# Schematic.net
KiCad netlist of a schematic drawn in Altium Designer
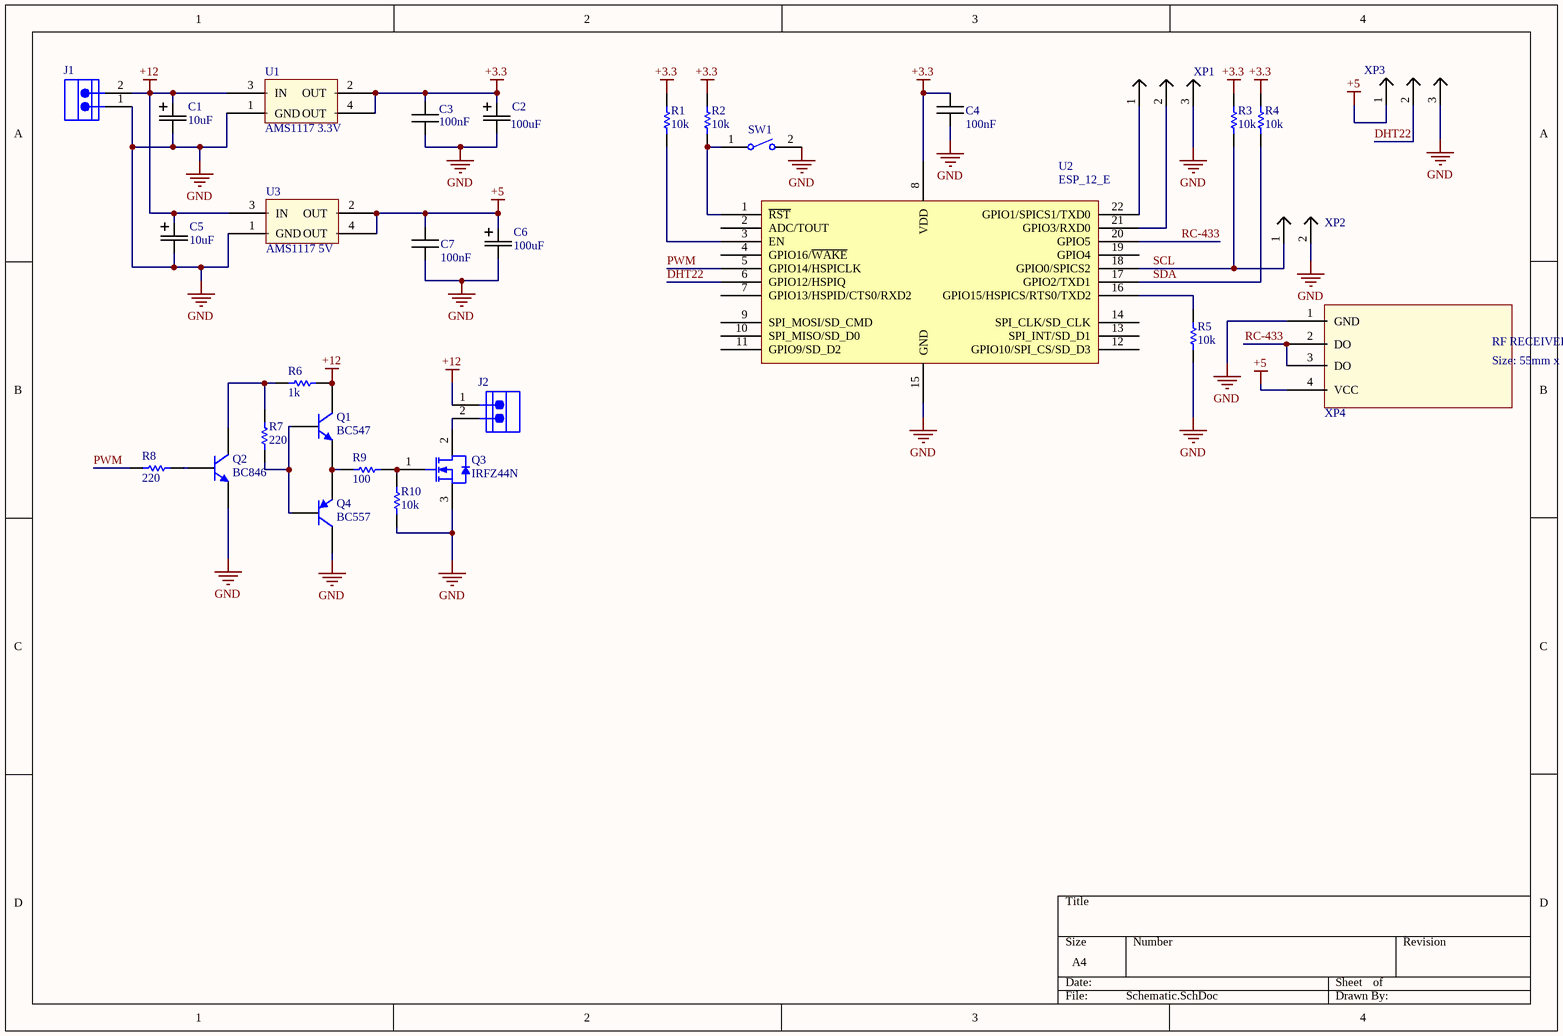
[diagram p0: Schematic.SchDoc]

(export (version "E")
  (design (tool "Eeschema 10.0.6"))
  (components
    (comp (ref "C1")
      (value "CAP_ELEC_5*11")
      (footprint "CAP_ELEC_5*11")
      (description "Electrolitic capacitor")
      (fields (field (name "VAL") "10uF"))
      (libsource (lib "altium-import") (part "root_1_CAP_ELEC_5*11_"))
    )
    (comp (ref "C2")
      (value "CAP_ELEC_8*11")
      (footprint "CAP_ELEC_8*11")
      (description "Electrolitic capacitor")
      (fields (field (name "VAL") "100uF"))
      (libsource (lib "altium-import") (part "root_1_CAP_ELEC_8*11_"))
    )
    (comp (ref "C3")
      (value "CAP_SMD")
      (footprint "CAP0805")
      (description "Ceramic capacitor, 0805")
      (fields (field (name "VAL") "100nF"))
      (libsource (lib "altium-import") (part "root_1_CAP_SMD_"))
    )
    (comp (ref "C4")
      (value "CAP_SMD")
      (footprint "CAP0805")
      (description "Ceramic capacitor, 0805")
      (fields (field (name "VAL") "100nF"))
      (libsource (lib "altium-import") (part "root_1_CAP_SMD_"))
    )
    (comp (ref "C5")
      (value "CAP_ELEC_5*11")
      (footprint "CAP_ELEC_5*11")
      (description "Electrolitic capacitor")
      (fields (field (name "VAL") "10uF"))
      (libsource (lib "altium-import") (part "root_1_CAP_ELEC_5*11_"))
    )
    (comp (ref "C6")
      (value "CAP_ELEC_8*11")
      (footprint "CAP_ELEC_8*11")
      (description "Electrolitic capacitor")
      (fields (field (name "VAL") "100uF"))
      (libsource (lib "altium-import") (part "root_1_CAP_ELEC_8*11_"))
    )
    (comp (ref "C7")
      (value "CAP_SMD")
      (footprint "CAP0805")
      (description "Ceramic capacitor, 0805")
      (fields (field (name "VAL") "100nF"))
      (libsource (lib "altium-import") (part "root_1_CAP_SMD_"))
    )
    (comp (ref "J1")
      (value "~")
      (footprint "KF350-3.5-02P")
      (fields
        (field (name "MANUFACTURER") "Cixi KaiFeng")
        (field (name "PARTNUMBER") "KF120-02P-14")
        (field (name "CONTACT") "Brass")
      )
      (libsource (lib "altium-import") (part "root_1_Terminal_2_"))
    )
    (comp (ref "J2")
      (value "~")
      (footprint "KF350-3.5-02P")
      (fields
        (field (name "MANUFACTURER") "Cixi KaiFeng")
        (field (name "PARTNUMBER") "KF120-02P-14")
        (field (name "CONTACT") "Brass")
      )
      (libsource (lib "altium-import") (part "root_3_Terminal_2_"))
    )
    (comp (ref "Q1")
      (value "BC547")
      (footprint "TO-92A")
      (description "NPN Bipolar Transistor")
      (fields (field (name "PUBLISHER") "Altium Limited"))
      (libsource (lib "altium-import") (part "root_0_BC547_"))
    )
    (comp (ref "Q2")
      (value "BC846")
      (footprint "SOT23 - 123")
      (description "NPN Bipolar Transistor")
      (fields (field (name "PUBLISHER") "Altium Limited"))
      (libsource (lib "altium-import") (part "root_0_BC846_"))
    )
    (comp (ref "Q3")
      (value "IRFZ44N")
      (footprint "TO-220")
      (description "N-channel Enhancement Mode Power MOSFET 49A/55V")
      (libsource (lib "altium-import") (part "root_0_IRFZ44N_"))
    )
    (comp (ref "Q4")
      (value "BC557")
      (footprint "TO-92A")
      (description "PNP Transistor")
      (fields (field (name "PUBLISHER") "Altium Limited"))
      (libsource (lib "altium-import") (part "root_2_mirrored_BC557_"))
    )
    (comp (ref "R1")
      (value "RES_SMD")
      (footprint "RES0805")
      (fields (field (name "VAL") "10k"))
      (libsource (lib "altium-import") (part "root_1_RES_SMD_"))
    )
    (comp (ref "R2")
      (value "RES_SMD")
      (footprint "RES0805")
      (fields (field (name "VAL") "10k"))
      (libsource (lib "altium-import") (part "root_1_RES_SMD_"))
    )
    (comp (ref "R3")
      (value "RES_SMD")
      (footprint "RES0805")
      (fields (field (name "VAL") "10k"))
      (libsource (lib "altium-import") (part "root_1_RES_SMD_"))
    )
    (comp (ref "R4")
      (value "RES_SMD")
      (footprint "RES0805")
      (fields (field (name "VAL") "10k"))
      (libsource (lib "altium-import") (part "root_1_RES_SMD_"))
    )
    (comp (ref "R5")
      (value "RES_SMD")
      (footprint "RES0805")
      (fields (field (name "VAL") "10k"))
      (libsource (lib "altium-import") (part "root_1_RES_SMD_"))
    )
    (comp (ref "R6")
      (value "RES_SMD")
      (footprint "RES0805")
      (fields (field (name "VAL") "1k"))
      (libsource (lib "altium-import") (part "root_2_RES_SMD_"))
    )
    (comp (ref "R7")
      (value "RES_SMD")
      (footprint "RES0805")
      (fields (field (name "VAL") "220"))
      (libsource (lib "altium-import") (part "root_3_RES_SMD_"))
    )
    (comp (ref "R8")
      (value "RES_SMD")
      (footprint "RES0805")
      (fields (field (name "VAL") "220"))
      (libsource (lib "altium-import") (part "root_2_RES_SMD_"))
    )
    (comp (ref "R9")
      (value "RES_SMD")
      (footprint "RES0805")
      (fields (field (name "VAL") "100"))
      (libsource (lib "altium-import") (part "root_2_RES_SMD_"))
    )
    (comp (ref "R10")
      (value "RES_SMD")
      (footprint "RES0805")
      (fields (field (name "VAL") "10k"))
      (libsource (lib "altium-import") (part "root_3_RES_SMD_"))
    )
    (comp (ref "SW1")
      (value "~")
      (footprint "SMD_BUT_6.3mm")
      (description "SMD Switch")
      (fields (field (name "MANUFACTURER") "TE Connectivity"))
      (libsource (lib "altium-import") (part "root_0_Button_2_SMD_"))
    )
    (comp (ref "U1")
      (value "AMS1117 3.3V")
      (footprint "SOT223-4")
      (description "Voltage regulator")
      (libsource (lib "altium-import") (part "root_0_AMS1117_"))
    )
    (comp (ref "U2")
      (value "ESP_12_E")
      (footprint "ESP_12_E")
      (description "ESP-12 Wi-Fi Module by AI-Thinker")
      (libsource (lib "altium-import") (part "root_0_ESP_12_E_"))
    )
    (comp (ref "U3")
      (value "AMS1117 5V")
      (footprint "SOT223-4")
      (description "Voltage regulator")
      (libsource (lib "altium-import") (part "root_0_AMS1117_"))
    )
    (comp (ref "XP1")
      (value "PLS-03")
      (footprint "PLS-03")
      (libsource (lib "altium-import") (part "root_1_PLS-03_"))
    )
    (comp (ref "XP2")
      (value "PLS-02")
      (footprint "PLS-02")
      (libsource (lib "altium-import") (part "root_1_PLS-02_"))
    )
    (comp (ref "XP3")
      (value "PBS-03")
      (footprint "PBS-03")
      (libsource (lib "altium-import") (part "root_1_PBS-03_"))
    )
    (comp (ref "XP4")
      (value "RF_RECEIVER")
      (footprint "RF RECEIVER")
      (libsource (lib "altium-import") (part "root_0_mirrored_RF_RECEIVER_"))
    )
  )
  (nets
    (net (code "1") (name "+3.3") (class "Default")
      (node (ref "C2") (pin "2") (pinfunction "2_2") (pintype "passive"))
      (node (ref "C3") (pin "2") (pinfunction "2_2") (pintype "passive"))
      (node (ref "C4") (pin "2") (pinfunction "2_2") (pintype "passive"))
      (node (ref "R1") (pin "2") (pinfunction "2_2") (pintype "passive"))
      (node (ref "R2") (pin "2") (pinfunction "2_2") (pintype "passive"))
      (node (ref "R3") (pin "2") (pinfunction "2_2") (pintype "passive"))
      (node (ref "R4") (pin "2") (pinfunction "2_2") (pintype "passive"))
      (node (ref "U1") (pin "2") (pinfunction "OUT_2") (pintype "passive"))
      (node (ref "U1") (pin "4") (pinfunction "OUT_4") (pintype "passive"))
      (node (ref "U2") (pin "8") (pinfunction "VDD_8") (pintype "passive"))
    )
    (net (code "2") (name "+5") (class "Default")
      (node (ref "C6") (pin "2") (pinfunction "2_2") (pintype "passive"))
      (node (ref "C7") (pin "2") (pinfunction "2_2") (pintype "passive"))
      (node (ref "U3") (pin "2") (pinfunction "OUT_2") (pintype "passive"))
      (node (ref "U3") (pin "4") (pinfunction "OUT_4") (pintype "passive"))
      (node (ref "XP3") (pin "1") (pinfunction "1_1") (pintype "passive"))
      (node (ref "XP4") (pin "4") (pinfunction "VCC_4") (pintype "passive"))
    )
    (net (code "3") (name "+12") (class "Default")
      (node (ref "C1") (pin "2") (pinfunction "2_2") (pintype "passive"))
      (node (ref "C5") (pin "2") (pinfunction "2_2") (pintype "passive"))
      (node (ref "J1") (pin "2") (pinfunction "2_2") (pintype "passive"))
      (node (ref "J2") (pin "1") (pinfunction "1_1") (pintype "passive"))
      (node (ref "Q1") (pin "1") (pinfunction "C_1") (pintype "passive"))
      (node (ref "R6") (pin "1") (pinfunction "1_1") (pintype "passive"))
      (node (ref "U1") (pin "3") (pinfunction "IN_3") (pintype "passive"))
      (node (ref "U3") (pin "3") (pinfunction "IN_3") (pintype "passive"))
    )
    (net (code "4") (name "/DHT22") (class "Default")
      (node (ref "U2") (pin "6") (pinfunction "GPIO12/HSPIQ_6") (pintype "passive"))
      (node (ref "XP3") (pin "2") (pinfunction "2_2") (pintype "passive"))
    )
    (net (code "5") (name "/PWM") (class "Default")
      (node (ref "R8") (pin "2") (pinfunction "2_2") (pintype "passive"))
      (node (ref "U2") (pin "5") (pinfunction "GPIO14/HSPICLK_5") (pintype "passive"))
    )
    (net (code "6") (name "/RC-433") (class "Default")
      (node (ref "U2") (pin "20") (pinfunction "GPIO5_20") (pintype "passive"))
      (node (ref "XP4") (pin "2") (pinfunction "DO_2") (pintype "passive"))
      (node (ref "XP4") (pin "3") (pinfunction "DO_3") (pintype "passive"))
    )
    (net (code "7") (name "/SCL") (class "Default")
      (node (ref "R3") (pin "1") (pinfunction "1_1") (pintype "passive"))
      (node (ref "U2") (pin "18") (pinfunction "GPIO0/SPICS2_18") (pintype "passive"))
      (node (ref "XP2") (pin "1") (pinfunction "1_1") (pintype "passive"))
    )
    (net (code "8") (name "/SDA") (class "Default")
      (node (ref "R4") (pin "1") (pinfunction "1_1") (pintype "passive"))
      (node (ref "U2") (pin "17") (pinfunction "GPIO2/TXD1_17") (pintype "passive"))
    )
    (net (code "9") (name "GND") (class "Default")
      (node (ref "C1") (pin "1") (pinfunction "1_1") (pintype "passive"))
      (node (ref "C2") (pin "1") (pinfunction "1_1") (pintype "passive"))
      (node (ref "C3") (pin "1") (pinfunction "1_1") (pintype "passive"))
      (node (ref "C4") (pin "1") (pinfunction "1_1") (pintype "passive"))
      (node (ref "C5") (pin "1") (pinfunction "1_1") (pintype "passive"))
      (node (ref "C6") (pin "1") (pinfunction "1_1") (pintype "passive"))
      (node (ref "C7") (pin "1") (pinfunction "1_1") (pintype "passive"))
      (node (ref "J1") (pin "1") (pinfunction "1_1") (pintype "passive"))
      (node (ref "Q2") (pin "3") (pinfunction "E_3") (pintype "passive"))
      (node (ref "Q3") (pin "3") (pinfunction "S_3") (pintype "passive"))
      (node (ref "Q4") (pin "1") (pinfunction "C_1") (pintype "passive"))
      (node (ref "R10") (pin "2") (pinfunction "2_2") (pintype "passive"))
      (node (ref "R5") (pin "1") (pinfunction "1_1") (pintype "passive"))
      (node (ref "SW1") (pin "2") (pinfunction "2_2") (pintype "passive"))
      (node (ref "U1") (pin "1") (pinfunction "GND_1") (pintype "passive"))
      (node (ref "U2") (pin "15") (pinfunction "GND_15") (pintype "passive"))
      (node (ref "U3") (pin "1") (pinfunction "GND_1") (pintype "passive"))
      (node (ref "XP1") (pin "3") (pinfunction "3_3") (pintype "passive"))
      (node (ref "XP2") (pin "2") (pinfunction "2_2") (pintype "passive"))
      (node (ref "XP3") (pin "3") (pinfunction "3_3") (pintype "passive"))
      (node (ref "XP4") (pin "1") (pinfunction "GND_1") (pintype "passive"))
    )
    (net (code "10") (name "Net-(Q1-B)") (class "Default")
      (node (ref "Q1") (pin "2") (pinfunction "B_2") (pintype "passive"))
      (node (ref "Q4") (pin "2") (pinfunction "B_2") (pintype "passive"))
      (node (ref "R7") (pin "2") (pinfunction "2_2") (pintype "passive"))
    )
    (net (code "11") (name "Net-(Q1-E)") (class "Default")
      (node (ref "Q1") (pin "3") (pinfunction "E_3") (pintype "passive"))
      (node (ref "Q4") (pin "3") (pinfunction "E_3") (pintype "passive"))
      (node (ref "R9") (pin "2") (pinfunction "2_2") (pintype "passive"))
    )
    (net (code "12") (name "Net-(Q2-B)") (class "Default")
      (node (ref "Q2") (pin "2") (pinfunction "B_2") (pintype "passive"))
      (node (ref "R8") (pin "1") (pinfunction "1_1") (pintype "passive"))
    )
    (net (code "13") (name "Net-(Q2-C)") (class "Default")
      (node (ref "Q2") (pin "1") (pinfunction "C_1") (pintype "passive"))
      (node (ref "R6") (pin "2") (pinfunction "2_2") (pintype "passive"))
      (node (ref "R7") (pin "1") (pinfunction "1_1") (pintype "passive"))
    )
    (net (code "14") (name "Net-(Q3-D)") (class "Default")
      (node (ref "J2") (pin "2") (pinfunction "2_2") (pintype "passive"))
      (node (ref "Q3") (pin "2") (pinfunction "D_2") (pintype "passive"))
    )
    (net (code "15") (name "Net-(Q3-G)") (class "Default")
      (node (ref "Q3") (pin "1") (pinfunction "G_1") (pintype "passive"))
      (node (ref "R10") (pin "1") (pinfunction "1_1") (pintype "passive"))
      (node (ref "R9") (pin "1") (pinfunction "1_1") (pintype "passive"))
    )
    (net (code "16") (name "Net-(U2-EN)") (class "Default")
      (node (ref "R1") (pin "1") (pinfunction "1_1") (pintype "passive"))
      (node (ref "U2") (pin "3") (pinfunction "EN_3") (pintype "passive"))
    )
    (net (code "17") (name "Net-(U2-GPIO1{slash}SPICS1{slash}TXD0)") (class "Default")
      (node (ref "U2") (pin "22") (pinfunction "GPIO1/SPICS1/TXD0_22") (pintype "passive"))
      (node (ref "XP1") (pin "1") (pinfunction "1_1") (pintype "passive"))
    )
    (net (code "18") (name "Net-(U2-GPIO3{slash}RXD0)") (class "Default")
      (node (ref "U2") (pin "21") (pinfunction "GPIO3/RXD0_21") (pintype "passive"))
      (node (ref "XP1") (pin "2") (pinfunction "2_2") (pintype "passive"))
    )
    (net (code "19") (name "Net-(U2-GPIO15{slash}HSPICS{slash}RTS0{slash}TXD2)") (class "Default")
      (node (ref "R5") (pin "2") (pinfunction "2_2") (pintype "passive"))
      (node (ref "U2") (pin "16") (pinfunction "GPIO15/HSPICS/RTS0/TXD2_16") (pintype "passive"))
    )
    (net (code "20") (name "Net-(U2-~{RST})") (class "Default")
      (node (ref "R2") (pin "1") (pinfunction "1_1") (pintype "passive"))
      (node (ref "SW1") (pin "1") (pinfunction "1_1") (pintype "passive"))
      (node (ref "U2") (pin "1") (pinfunction "~{RST}_1") (pintype "passive"))
    )
    (net (code "21") (name "unconnected-(U2-ADC{slash}TOUT-Pad2)") (class "Default")
      (node (ref "U2") (pin "2") (pinfunction "ADC/TOUT_2") (pintype "passive"))
    )
    (net (code "22") (name "unconnected-(U2-GPIO4-Pad19)") (class "Default")
      (node (ref "U2") (pin "19") (pinfunction "GPIO4_19") (pintype "passive"))
    )
    (net (code "23") (name "unconnected-(U2-GPIO9{slash}SD_D2-Pad11)") (class "Default")
      (node (ref "U2") (pin "11") (pinfunction "GPIO9/SD_D2_11") (pintype "passive"))
    )
    (net (code "24") (name "unconnected-(U2-GPIO10{slash}SPI_CS{slash}SD_D3-Pad12)") (class "Default")
      (node (ref "U2") (pin "12") (pinfunction "GPIO10/SPI_CS/SD_D3_12") (pintype "passive"))
    )
    (net (code "25") (name "unconnected-(U2-GPIO13{slash}HSPID{slash}CTS0{slash}RXD2-Pad7)") (class "Default")
      (node (ref "U2") (pin "7") (pinfunction "GPIO13/HSPID/CTS0/RXD2_7") (pintype "passive"))
    )
    (net (code "26") (name "unconnected-(U2-GPIO16{slash}~{WAKE}-Pad4)") (class "Default")
      (node (ref "U2") (pin "4") (pinfunction "GPIO16/~{WAKE}_4") (pintype "passive"))
    )
    (net (code "27") (name "unconnected-(U2-SPI_CLK{slash}SD_CLK-Pad14)") (class "Default")
      (node (ref "U2") (pin "14") (pinfunction "SPI_CLK/SD_CLK_14") (pintype "passive"))
    )
    (net (code "28") (name "unconnected-(U2-SPI_INT{slash}SD_D1-Pad13)") (class "Default")
      (node (ref "U2") (pin "13") (pinfunction "SPI_INT/SD_D1_13") (pintype "passive"))
    )
    (net (code "29") (name "unconnected-(U2-SPI_MISO{slash}SD_D0-Pad10)") (class "Default")
      (node (ref "U2") (pin "10") (pinfunction "SPI_MISO/SD_D0_10") (pintype "passive"))
    )
    (net (code "30") (name "unconnected-(U2-SPI_MOSI{slash}SD_CMD-Pad9)") (class "Default")
      (node (ref "U2") (pin "9") (pinfunction "SPI_MOSI/SD_CMD_9") (pintype "passive"))
    )
  )
)
